# tm5.net
KiCad netlist of a schematic drawn in EAGLE
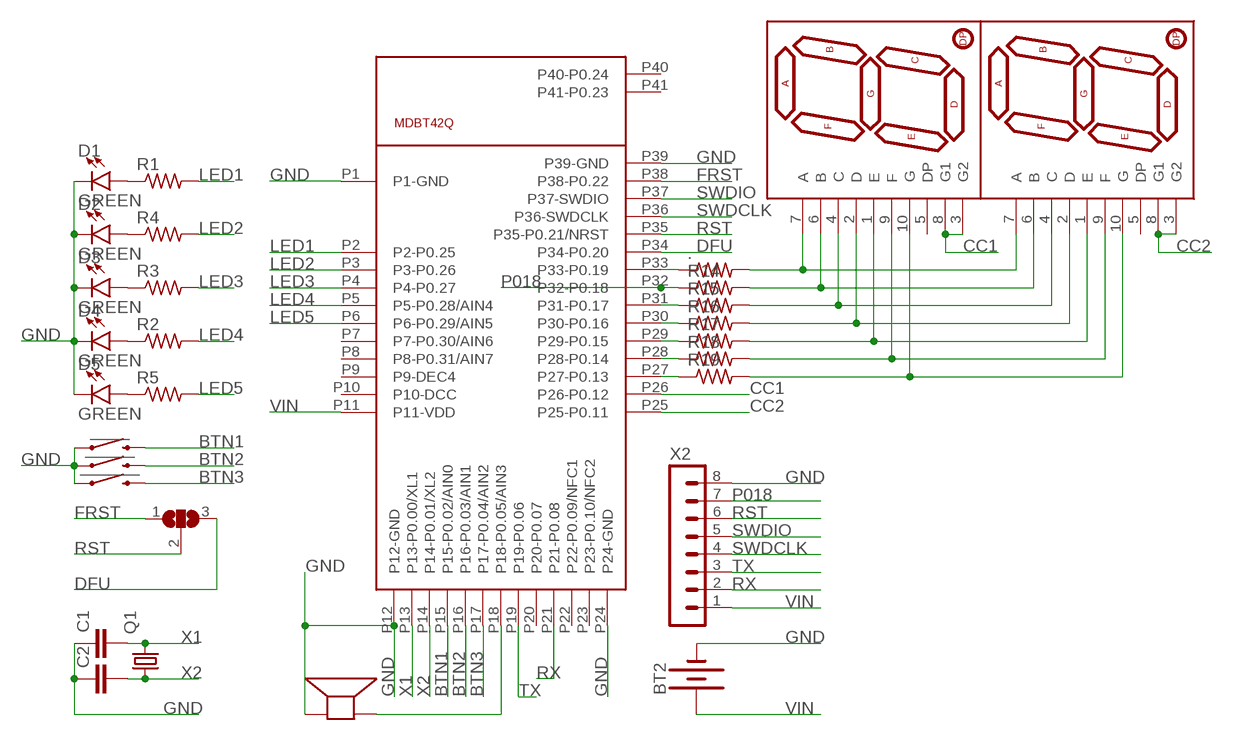
[diagram p0: schematic, sheet 1]

(export (version "E")
  (design (tool "Eeschema 10.0.6"))
  (components
    (comp (ref ".")
      (value "R-US_R0603")
      (footprint "eagle-import:R0603")
      (libsource (lib "eagle-import") (part "R-US_R0603"))
    )
    (comp (ref "BT2")
      (value "BATTERY-20MM_SMD_4LEGS_OVERPASTE")
      (footprint "eagle-import:BATTCON_20MM_4LEGS_OVERPASTE")
      (libsource (lib "eagle-import") (part "BATTERY-20MM_SMD_4LEGS_OVERPASTE"))
    )
    (comp (ref "C1")
      (value "C-EUC0603")
      (footprint "eagle-import:C0603")
      (libsource (lib "eagle-import") (part "C-EUC0603"))
    )
    (comp (ref "C2")
      (value "C-EUC0603")
      (footprint "eagle-import:C0603")
      (libsource (lib "eagle-import") (part "C-EUC0603"))
    )
    (comp (ref "CFG")
      (value "SJ2W")
      (footprint "eagle-import:SJ_2")
      (libsource (lib "eagle-import") (part "SJ2W"))
    )
    (comp (ref "D1")
      (value "GREEN")
      (footprint "eagle-import:LED-1206")
      (libsource (lib "eagle-import") (part "LED-GREEN1206"))
    )
    (comp (ref "D2")
      (value "GREEN")
      (footprint "eagle-import:LED-1206")
      (libsource (lib "eagle-import") (part "LED-GREEN1206"))
    )
    (comp (ref "D3")
      (value "GREEN")
      (footprint "eagle-import:LED-1206")
      (libsource (lib "eagle-import") (part "LED-GREEN1206"))
    )
    (comp (ref "D4")
      (value "GREEN")
      (footprint "eagle-import:LED-1206")
      (libsource (lib "eagle-import") (part "LED-GREEN1206"))
    )
    (comp (ref "D5")
      (value "GREEN")
      (footprint "eagle-import:LED-1206")
      (libsource (lib "eagle-import") (part "LED-GREEN1206"))
    )
    (comp (ref "Q1")
      (value "KX-327-NHT")
      (footprint "eagle-import:3.2X1.5")
      (libsource (lib "eagle-import") (part "KX-327-NHT"))
    )
    (comp (ref "R1")
      (value "R-US_R0603")
      (footprint "eagle-import:R0603")
      (libsource (lib "eagle-import") (part "R-US_R0603"))
    )
    (comp (ref "R2")
      (value "R-US_R0603")
      (footprint "eagle-import:R0603")
      (libsource (lib "eagle-import") (part "R-US_R0603"))
    )
    (comp (ref "R3")
      (value "R-US_R0603")
      (footprint "eagle-import:R0603")
      (libsource (lib "eagle-import") (part "R-US_R0603"))
    )
    (comp (ref "R4")
      (value "R-US_R0603")
      (footprint "eagle-import:R0603")
      (libsource (lib "eagle-import") (part "R-US_R0603"))
    )
    (comp (ref "R5")
      (value "R-US_R0603")
      (footprint "eagle-import:R0603")
      (libsource (lib "eagle-import") (part "R-US_R0603"))
    )
    (comp (ref "R14")
      (value "R-US_R0603")
      (footprint "eagle-import:R0603")
      (libsource (lib "eagle-import") (part "R-US_R0603"))
    )
    (comp (ref "R15")
      (value "R-US_R0603")
      (footprint "eagle-import:R0603")
      (libsource (lib "eagle-import") (part "R-US_R0603"))
    )
    (comp (ref "R16")
      (value "R-US_R0603")
      (footprint "eagle-import:R0603")
      (libsource (lib "eagle-import") (part "R-US_R0603"))
    )
    (comp (ref "R17")
      (value "R-US_R0603")
      (footprint "eagle-import:R0603")
      (libsource (lib "eagle-import") (part "R-US_R0603"))
    )
    (comp (ref "R18")
      (value "R-US_R0603")
      (footprint "eagle-import:R0603")
      (libsource (lib "eagle-import") (part "R-US_R0603"))
    )
    (comp (ref "R19")
      (value "R-US_R0603")
      (footprint "eagle-import:R0603")
      (libsource (lib "eagle-import") (part "R-US_R0603"))
    )
    (comp (ref "SPK1")
      (value "SMT-0540-S-R")
      (footprint "eagle-import:SMT-0540-S-R")
      (libsource (lib "eagle-import") (part "SMT-0540-S-R"))
    )
    (comp (ref "U$1")
      (value "MDBT42Q")
      (footprint "eagle-import:MDBT40")
      (libsource (lib "eagle-import") (part "MDBT42Q"))
    )
    (comp (ref "U$2")
      (value "7-SEGMENT-DISPLAY-1\"-RED")
      (footprint "eagle-import:7-SEGMENT-SMD")
      (libsource (lib "eagle-import") (part "7-SEGMENT-DISPLAY-1{dblquote}-RED"))
    )
    (comp (ref "U$3")
      (value "7-SEGMENT-DISPLAY-1\"-RED")
      (footprint "eagle-import:7-SEGMENT-SMD")
      (libsource (lib "eagle-import") (part "7-SEGMENT-DISPLAY-1{dblquote}-RED"))
    )
    (comp (ref "X2")
      (value "SM08B-SRSS-TB")
      (footprint "eagle-import:SM08B-SRSS-TB")
      (libsource (lib "eagle-import") (part "SM08B-SRSS-TB"))
    )
    (comp (ref "____")
      (value "MOMENTARY-SWITCH-SPST-SMD-6.2MM-TALL")
      (footprint "eagle-import:TACTILE_SWITCH_SMD_6.2MM_TALL")
      (libsource (lib "eagle-import") (part "MOMENTARY-SWITCH-SPST-SMD-6.2MM-TALL"))
    )
    (comp (ref "_____")
      (value "MOMENTARY-SWITCH-SPST-SMD-6.2MM-TALL")
      (footprint "eagle-import:TACTILE_SWITCH_SMD_6.2MM_TALL")
      (libsource (lib "eagle-import") (part "MOMENTARY-SWITCH-SPST-SMD-6.2MM-TALL"))
    )
    (comp (ref "______")
      (value "MOMENTARY-SWITCH-SPST-SMD-6.2MM-TALL")
      (footprint "eagle-import:TACTILE_SWITCH_SMD_6.2MM_TALL")
      (libsource (lib "eagle-import") (part "MOMENTARY-SWITCH-SPST-SMD-6.2MM-TALL"))
    )
  )
  (nets
    (net (code "1") (name "/BTN1") (class "Default")
      (node (ref "U$1") (pin "P15") (pinfunction "P15-P0.02/AIN0_P15") (pintype "bidirectional"))
      (node (ref "____") (pin "B2") (pinfunction "2_B2") (pintype "passive"))
    )
    (net (code "2") (name "/BTN2") (class "Default")
      (node (ref "U$1") (pin "P16") (pinfunction "P16-P0.03/AIN1_P16") (pintype "bidirectional"))
      (node (ref "_____") (pin "B2") (pinfunction "2_B2") (pintype "passive"))
    )
    (net (code "3") (name "/BTN3") (class "Default")
      (node (ref "U$1") (pin "P17") (pinfunction "P17-P0.04/AIN2_P17") (pintype "bidirectional"))
      (node (ref "______") (pin "B2") (pinfunction "2_B2") (pintype "passive"))
    )
    (net (code "4") (name "/CC1") (class "Default")
      (node (ref "U$1") (pin "P26") (pinfunction "P26-P0.12_P26") (pintype "bidirectional"))
      (node (ref "U$2") (pin "3") (pinfunction "G2_3") (pintype "bidirectional"))
      (node (ref "U$2") (pin "8") (pinfunction "G1_8") (pintype "bidirectional"))
    )
    (net (code "5") (name "/CC2") (class "Default")
      (node (ref "U$1") (pin "P25") (pinfunction "P25-P0.11_P25") (pintype "bidirectional"))
      (node (ref "U$3") (pin "3") (pinfunction "G2_3") (pintype "bidirectional"))
      (node (ref "U$3") (pin "8") (pinfunction "G1_8") (pintype "bidirectional"))
    )
    (net (code "6") (name "/DFU") (class "Default")
      (node (ref "CFG") (pin "3") (pinfunction "3_3") (pintype "passive"))
      (node (ref "U$1") (pin "P34") (pinfunction "P34-P0.20_P34") (pintype "bidirectional"))
    )
    (net (code "7") (name "/FRST") (class "Default")
      (node (ref "CFG") (pin "1") (pinfunction "1_1") (pintype "passive"))
      (node (ref "U$1") (pin "P38") (pinfunction "P38-P0.22_P38") (pintype "bidirectional"))
    )
    (net (code "8") (name "/GND") (class "Default")
      (node (ref "BT2") (pin "2") (pinfunction "-_2") (pintype "power_in"))
      (node (ref "C1") (pin "1") (pinfunction "1_1") (pintype "passive"))
      (node (ref "C2") (pin "1") (pinfunction "1_1") (pintype "passive"))
      (node (ref "D1") (pin "C") (pinfunction "C_C") (pintype "passive"))
      (node (ref "D2") (pin "C") (pinfunction "C_C") (pintype "passive"))
      (node (ref "D3") (pin "C") (pinfunction "C_C") (pintype "passive"))
      (node (ref "D4") (pin "C") (pinfunction "C_C") (pintype "passive"))
      (node (ref "D5") (pin "C") (pinfunction "C_C") (pintype "passive"))
      (node (ref "SPK1") (pin "-") (pinfunction "+_-") (pintype "passive"))
      (node (ref "U$1") (pin "P1") (pinfunction "P1-GND_P1") (pintype "bidirectional"))
      (node (ref "U$1") (pin "P12") (pinfunction "P12-GND_P12") (pintype "bidirectional"))
      (node (ref "U$1") (pin "P24") (pinfunction "P24-GND_P24") (pintype "bidirectional"))
      (node (ref "U$1") (pin "P39") (pinfunction "P39-GND_P39") (pintype "bidirectional"))
      (node (ref "X2") (pin "8") (pinfunction "8_8") (pintype "passive"))
      (node (ref "____") (pin "A2") (pinfunction "1_A2") (pintype "passive"))
      (node (ref "_____") (pin "A2") (pinfunction "1_A2") (pintype "passive"))
      (node (ref "______") (pin "A2") (pinfunction "1_A2") (pintype "passive"))
    )
    (net (code "9") (name "/LED1") (class "Default")
      (node (ref "R1") (pin "2") (pinfunction "2_2") (pintype "passive"))
      (node (ref "U$1") (pin "P2") (pinfunction "P2-P0.25_P2") (pintype "bidirectional"))
    )
    (net (code "10") (name "/LED2") (class "Default")
      (node (ref "R4") (pin "2") (pinfunction "2_2") (pintype "passive"))
      (node (ref "U$1") (pin "P3") (pinfunction "P3-P0.26_P3") (pintype "bidirectional"))
    )
    (net (code "11") (name "/LED3") (class "Default")
      (node (ref "R3") (pin "2") (pinfunction "2_2") (pintype "passive"))
      (node (ref "U$1") (pin "P4") (pinfunction "P4-P0.27_P4") (pintype "bidirectional"))
    )
    (net (code "12") (name "/LED4") (class "Default")
      (node (ref "R2") (pin "2") (pinfunction "2_2") (pintype "passive"))
      (node (ref "U$1") (pin "P5") (pinfunction "P5-P0.28/AIN4_P5") (pintype "bidirectional"))
    )
    (net (code "13") (name "/LED5") (class "Default")
      (node (ref "R5") (pin "2") (pinfunction "2_2") (pintype "passive"))
      (node (ref "U$1") (pin "P6") (pinfunction "P6-P0.29/AIN5_P6") (pintype "bidirectional"))
    )
    (net (code "14") (name "/P018") (class "Default")
      (node (ref "R14") (pin "1") (pinfunction "1_1") (pintype "passive"))
      (node (ref "U$1") (pin "P32") (pinfunction "P32-P0.18_P32") (pintype "bidirectional"))
      (node (ref "X2") (pin "7") (pinfunction "7_7") (pintype "passive"))
    )
    (net (code "15") (name "/RST") (class "Default")
      (node (ref "CFG") (pin "2") (pinfunction "2_2") (pintype "passive"))
      (node (ref "U$1") (pin "P35") (pinfunction "P35-P0.21/NRST_P35") (pintype "bidirectional"))
      (node (ref "X2") (pin "6") (pinfunction "6_6") (pintype "passive"))
    )
    (net (code "16") (name "/RX") (class "Default")
      (node (ref "U$1") (pin "P21") (pinfunction "P21-P0.08_P21") (pintype "bidirectional"))
      (node (ref "X2") (pin "2") (pinfunction "2_2") (pintype "passive"))
    )
    (net (code "17") (name "/SWDCLK") (class "Default")
      (node (ref "U$1") (pin "P36") (pinfunction "P36-SWDCLK_P36") (pintype "bidirectional"))
      (node (ref "X2") (pin "4") (pinfunction "4_4") (pintype "passive"))
    )
    (net (code "18") (name "/SWDIO") (class "Default")
      (node (ref "U$1") (pin "P37") (pinfunction "P37-SWDIO_P37") (pintype "bidirectional"))
      (node (ref "X2") (pin "5") (pinfunction "5_5") (pintype "passive"))
    )
    (net (code "19") (name "/TX") (class "Default")
      (node (ref "U$1") (pin "P19") (pinfunction "P19-P0.06_P19") (pintype "bidirectional"))
      (node (ref "X2") (pin "3") (pinfunction "3_3") (pintype "passive"))
    )
    (net (code "20") (name "/VIN") (class "Default")
      (node (ref "BT2") (pin "1") (pinfunction "+_1") (pintype "power_in"))
      (node (ref "U$1") (pin "P11") (pinfunction "P11-VDD_P11") (pintype "bidirectional"))
      (node (ref "X2") (pin "1") (pinfunction "1_1") (pintype "passive"))
    )
    (net (code "21") (name "/X1") (class "Default")
      (node (ref "C1") (pin "2") (pinfunction "2_2") (pintype "passive"))
      (node (ref "Q1") (pin "2") (pinfunction "2_2") (pintype "passive"))
      (node (ref "U$1") (pin "P13") (pinfunction "P13-P0.00/XL1_P13") (pintype "bidirectional"))
    )
    (net (code "22") (name "/X2") (class "Default")
      (node (ref "C2") (pin "2") (pinfunction "2_2") (pintype "passive"))
      (node (ref "Q1") (pin "1") (pinfunction "1_1") (pintype "passive"))
      (node (ref "U$1") (pin "P14") (pinfunction "P14-P0.01/XL2_P14") (pintype "bidirectional"))
    )
    (net (code "23") (name "Net-(D1-PadA)") (class "Default")
      (node (ref "D1") (pin "A") (pinfunction "A_A") (pintype "passive"))
      (node (ref "R1") (pin "1") (pinfunction "1_1") (pintype "passive"))
    )
    (net (code "24") (name "Net-(D2-PadA)") (class "Default")
      (node (ref "D2") (pin "A") (pinfunction "A_A") (pintype "passive"))
      (node (ref "R4") (pin "1") (pinfunction "1_1") (pintype "passive"))
    )
    (net (code "25") (name "Net-(D3-PadA)") (class "Default")
      (node (ref "D3") (pin "A") (pinfunction "A_A") (pintype "passive"))
      (node (ref "R3") (pin "1") (pinfunction "1_1") (pintype "passive"))
    )
    (net (code "26") (name "Net-(D4-PadA)") (class "Default")
      (node (ref "D4") (pin "A") (pinfunction "A_A") (pintype "passive"))
      (node (ref "R2") (pin "1") (pinfunction "1_1") (pintype "passive"))
    )
    (net (code "27") (name "Net-(D5-PadA)") (class "Default")
      (node (ref "D5") (pin "A") (pinfunction "A_A") (pintype "passive"))
      (node (ref "R5") (pin "1") (pinfunction "1_1") (pintype "passive"))
    )
    (net (code "28") (name "Net-(SPK1--)") (class "Default")
      (node (ref "SPK1") (pin "+") (pinfunction "-_+") (pintype "passive"))
      (node (ref "U$1") (pin "P18") (pinfunction "P18-P0.05/AIN3_P18") (pintype "bidirectional"))
    )
    (net (code "29") (name "Net-(U$1-P27-P0.13)") (class "Default")
      (node (ref "R19") (pin "1") (pinfunction "1_1") (pintype "passive"))
      (node (ref "U$1") (pin "P27") (pinfunction "P27-P0.13_P27") (pintype "bidirectional"))
    )
    (net (code "30") (name "Net-(U$1-P28-P0.14)") (class "Default")
      (node (ref "R18") (pin "1") (pinfunction "1_1") (pintype "passive"))
      (node (ref "U$1") (pin "P28") (pinfunction "P28-P0.14_P28") (pintype "bidirectional"))
    )
    (net (code "31") (name "Net-(U$1-P29-P0.15)") (class "Default")
      (node (ref "R17") (pin "1") (pinfunction "1_1") (pintype "passive"))
      (node (ref "U$1") (pin "P29") (pinfunction "P29-P0.15_P29") (pintype "bidirectional"))
    )
    (net (code "32") (name "Net-(U$1-P30-P0.16)") (class "Default")
      (node (ref "R16") (pin "1") (pinfunction "1_1") (pintype "passive"))
      (node (ref "U$1") (pin "P30") (pinfunction "P30-P0.16_P30") (pintype "bidirectional"))
    )
    (net (code "33") (name "Net-(U$1-P31-P0.17)") (class "Default")
      (node (ref "R15") (pin "1") (pinfunction "1_1") (pintype "passive"))
      (node (ref "U$1") (pin "P31") (pinfunction "P31-P0.17_P31") (pintype "bidirectional"))
    )
    (net (code "34") (name "Net-(U$1-P33-P0.19)") (class "Default")
      (node (ref ".") (pin "1") (pinfunction "1_1") (pintype "passive"))
      (node (ref "U$1") (pin "P33") (pinfunction "P33-P0.19_P33") (pintype "bidirectional"))
    )
    (net (code "35") (name "Net-(U$2-A)") (class "Default")
      (node (ref ".") (pin "2") (pinfunction "2_2") (pintype "passive"))
      (node (ref "U$2") (pin "7") (pinfunction "A_7") (pintype "bidirectional"))
      (node (ref "U$3") (pin "7") (pinfunction "A_7") (pintype "bidirectional"))
    )
    (net (code "36") (name "Net-(U$2-B)") (class "Default")
      (node (ref "R14") (pin "2") (pinfunction "2_2") (pintype "passive"))
      (node (ref "U$2") (pin "6") (pinfunction "B_6") (pintype "bidirectional"))
      (node (ref "U$3") (pin "6") (pinfunction "B_6") (pintype "bidirectional"))
    )
    (net (code "37") (name "Net-(U$2-C)") (class "Default")
      (node (ref "R15") (pin "2") (pinfunction "2_2") (pintype "passive"))
      (node (ref "U$2") (pin "4") (pinfunction "C_4") (pintype "bidirectional"))
      (node (ref "U$3") (pin "4") (pinfunction "C_4") (pintype "bidirectional"))
    )
    (net (code "38") (name "Net-(U$2-D)") (class "Default")
      (node (ref "R16") (pin "2") (pinfunction "2_2") (pintype "passive"))
      (node (ref "U$2") (pin "2") (pinfunction "D_2") (pintype "bidirectional"))
      (node (ref "U$3") (pin "2") (pinfunction "D_2") (pintype "bidirectional"))
    )
    (net (code "39") (name "Net-(U$2-E)") (class "Default")
      (node (ref "R17") (pin "2") (pinfunction "2_2") (pintype "passive"))
      (node (ref "U$2") (pin "1") (pinfunction "E_1") (pintype "bidirectional"))
      (node (ref "U$3") (pin "1") (pinfunction "E_1") (pintype "bidirectional"))
    )
    (net (code "40") (name "Net-(U$2-F)") (class "Default")
      (node (ref "R18") (pin "2") (pinfunction "2_2") (pintype "passive"))
      (node (ref "U$2") (pin "9") (pinfunction "F_9") (pintype "bidirectional"))
      (node (ref "U$3") (pin "9") (pinfunction "F_9") (pintype "bidirectional"))
    )
    (net (code "41") (name "Net-(U$2-G)") (class "Default")
      (node (ref "R19") (pin "2") (pinfunction "2_2") (pintype "passive"))
      (node (ref "U$2") (pin "10") (pinfunction "G_10") (pintype "bidirectional"))
      (node (ref "U$3") (pin "10") (pinfunction "G_10") (pintype "bidirectional"))
    )
    (net (code "42") (name "unconnected-(U$1-P7-P0.30{slash}AIN6-PadP7)") (class "Default")
      (node (ref "U$1") (pin "P7") (pinfunction "P7-P0.30/AIN6_P7") (pintype "bidirectional"))
    )
    (net (code "43") (name "unconnected-(U$1-P8-P0.31{slash}AIN7-PadP8)") (class "Default")
      (node (ref "U$1") (pin "P8") (pinfunction "P8-P0.31/AIN7_P8") (pintype "bidirectional"))
    )
    (net (code "44") (name "unconnected-(U$1-P9-DEC4-PadP9)") (class "Default")
      (node (ref "U$1") (pin "P9") (pinfunction "P9-DEC4_P9") (pintype "bidirectional"))
    )
    (net (code "45") (name "unconnected-(U$1-P10-DCC-PadP10)") (class "Default")
      (node (ref "U$1") (pin "P10") (pinfunction "P10-DCC_P10") (pintype "bidirectional"))
    )
    (net (code "46") (name "unconnected-(U$1-P20-P0.07-PadP20)") (class "Default")
      (node (ref "U$1") (pin "P20") (pinfunction "P20-P0.07_P20") (pintype "bidirectional"))
    )
    (net (code "47") (name "unconnected-(U$1-P22-P0.09{slash}NFC1-PadP22)") (class "Default")
      (node (ref "U$1") (pin "P22") (pinfunction "P22-P0.09/NFC1_P22") (pintype "bidirectional"))
    )
    (net (code "48") (name "unconnected-(U$1-P23-P0.10{slash}NFC2-PadP23)") (class "Default")
      (node (ref "U$1") (pin "P23") (pinfunction "P23-P0.10/NFC2_P23") (pintype "bidirectional"))
    )
    (net (code "49") (name "unconnected-(U$1-P40-P0.24-PadP40)") (class "Default")
      (node (ref "U$1") (pin "P40") (pinfunction "P40-P0.24_P40") (pintype "bidirectional"))
    )
    (net (code "50") (name "unconnected-(U$1-P41-P0.23-PadP41)") (class "Default")
      (node (ref "U$1") (pin "P41") (pinfunction "P41-P0.23_P41") (pintype "bidirectional"))
    )
    (net (code "51") (name "unconnected-(U$2-DP-Pad5)") (class "Default")
      (node (ref "U$2") (pin "5") (pinfunction "DP_5") (pintype "bidirectional"))
    )
    (net (code "52") (name "unconnected-(U$3-DP-Pad5)") (class "Default")
      (node (ref "U$3") (pin "5") (pinfunction "DP_5") (pintype "bidirectional"))
    )
  )
)
